# PCB_Draft_3.net
KiCad netlist of a schematic drawn in EAGLE
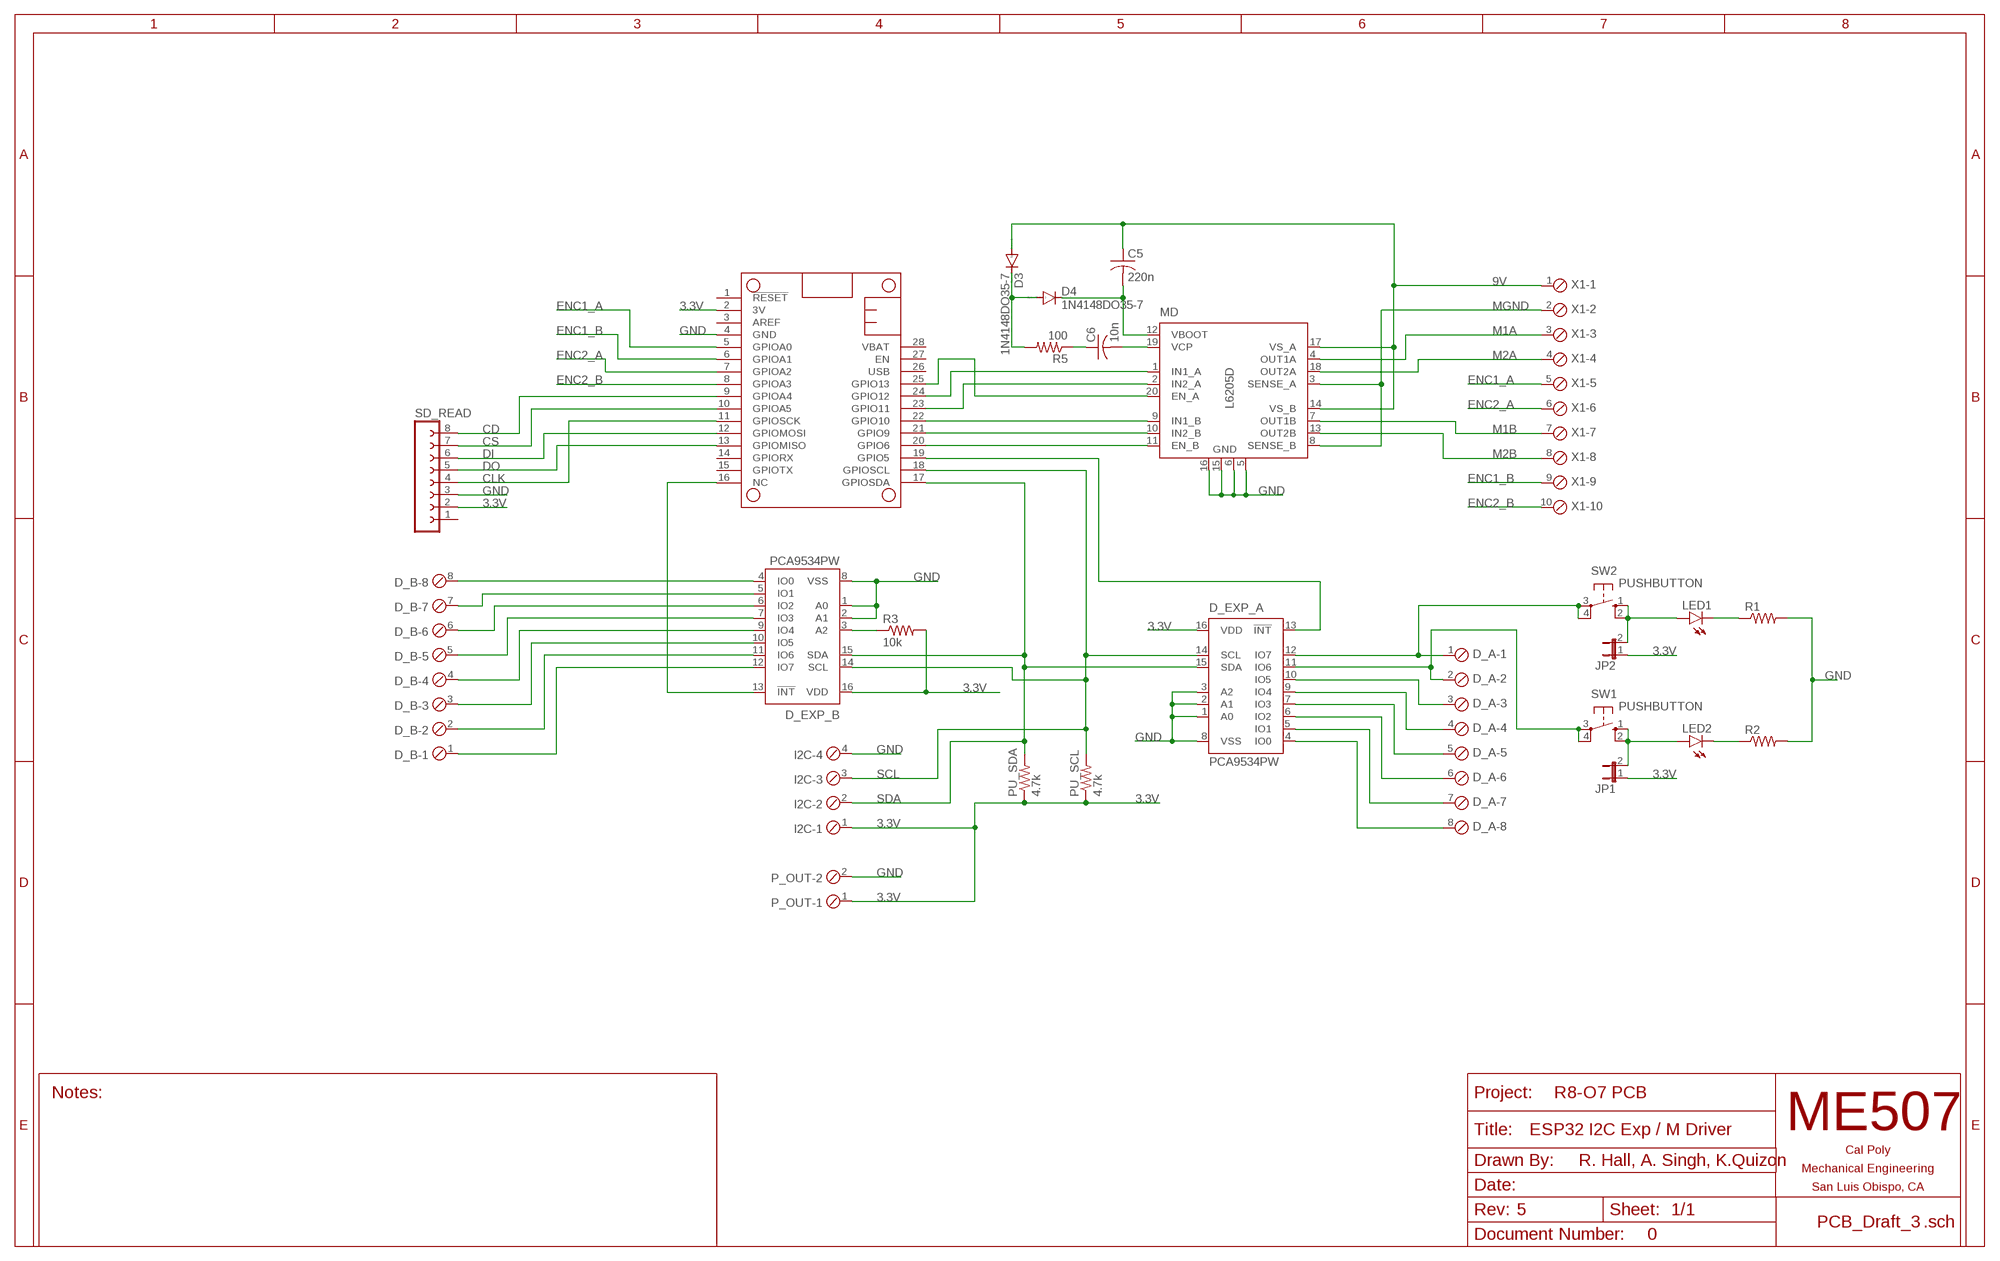
[diagram p0: schematic, sheet 1]

(export (version "E")
  (design (tool "Eeschema 10.0.6"))
  (components
    (comp (ref "C5")
      (value "220n")
      (footprint "eagle-import:C0805")
      (libsource (lib "eagle-import") (part "C-USC0805"))
    )
    (comp (ref "C6")
      (value "10n")
      (footprint "eagle-import:C0805")
      (libsource (lib "eagle-import") (part "C-USC0805"))
    )
    (comp (ref "D3")
      (value "1N4148DO35-7")
      (footprint "eagle-import:DO35-7")
      (libsource (lib "eagle-import") (part "1N4148DO35-7"))
    )
    (comp (ref "D4")
      (value "1N4148DO35-7")
      (footprint "eagle-import:DO35-7")
      (libsource (lib "eagle-import") (part "1N4148DO35-7"))
    )
    (comp (ref "D_A")
      (value "SCREWTERM_8P_254")
      (footprint "eagle-import:8POL254")
      (libsource (lib "eagle-import") (part "SCREWTERM_8P_254"))
    )
    (comp (ref "D_B")
      (value "SCREWTERM_8P_254")
      (footprint "eagle-import:8POL254")
      (libsource (lib "eagle-import") (part "SCREWTERM_8P_254"))
    )
    (comp (ref "D_EXP_A")
      (value "PCA9534PW")
      (footprint "eagle-import:TSSOP16")
      (libsource (lib "eagle-import") (part "PCA9534PW"))
    )
    (comp (ref "D_EXP_B")
      (value "PCA9534PW")
      (footprint "eagle-import:TSSOP16")
      (libsource (lib "eagle-import") (part "PCA9534PW"))
    )
    (comp (ref "FTHRWNG")
      (value "FEATHERWINGEXTENDED_BOTH_ENDS")
      (footprint "eagle-import:FEATHERWING")
      (libsource (lib "eagle-import") (part "FEATHERWINGEXTENDED_BOTH_ENDS"))
    )
    (comp (ref "I2C")
      (value "SCREWTERM_4P_254")
      (footprint "eagle-import:4POL254")
      (libsource (lib "eagle-import") (part "SCREWTERM_4P_254"))
    )
    (comp (ref "JP1")
      (value "JP1E")
      (footprint "eagle-import:JP1")
      (libsource (lib "eagle-import") (part "JP1E"))
    )
    (comp (ref "JP2")
      (value "JP1E")
      (footprint "eagle-import:JP1")
      (libsource (lib "eagle-import") (part "JP1E"))
    )
    (comp (ref "LED1")
      (value "LEDCHIPLED_0805")
      (footprint "eagle-import:CHIPLED_0805")
      (libsource (lib "eagle-import") (part "LEDCHIPLED_0805"))
    )
    (comp (ref "LED2")
      (value "LEDCHIPLED_0805")
      (footprint "eagle-import:CHIPLED_0805")
      (libsource (lib "eagle-import") (part "LEDCHIPLED_0805"))
    )
    (comp (ref "MD")
      (value "L6205D")
      (footprint "eagle-import:SO20")
      (libsource (lib "eagle-import") (part "L6205D"))
    )
    (comp (ref "PU_SCL")
      (value "4.7k")
      (footprint "eagle-import:M0805")
      (libsource (lib "eagle-import") (part "R-US_M0805"))
    )
    (comp (ref "PU_SDA")
      (value "4.7k")
      (footprint "eagle-import:M0805")
      (libsource (lib "eagle-import") (part "R-US_M0805"))
    )
    (comp (ref "P_OUT")
      (value "SCREWTERM_2P_254")
      (footprint "eagle-import:2POL254")
      (libsource (lib "eagle-import") (part "SCREWTERM_2P_254"))
    )
    (comp (ref "R1")
      (value "R-US_M0805")
      (footprint "eagle-import:M0805")
      (libsource (lib "eagle-import") (part "R-US_M0805"))
    )
    (comp (ref "R2")
      (value "R-US_M0805")
      (footprint "eagle-import:M0805")
      (libsource (lib "eagle-import") (part "R-US_M0805"))
    )
    (comp (ref "R3")
      (value "10k")
      (footprint "eagle-import:M0805")
      (libsource (lib "eagle-import") (part "R-US_M0805"))
    )
    (comp (ref "R5")
      (value "100")
      (footprint "eagle-import:M0805")
      (libsource (lib "eagle-import") (part "R-US_M0805"))
    )
    (comp (ref "SD_READ")
      (value "FE08-1")
      (footprint "eagle-import:FE08")
      (libsource (lib "eagle-import") (part "FE08-1"))
    )
    (comp (ref "SW1")
      (value "PUSHBUTTON")
      (footprint "eagle-import:B3F-10XX")
      (fields (field (name "MPN") "B3F-1000"))
      (libsource (lib "eagle-import") (part "PUSHBUTTON"))
    )
    (comp (ref "SW2")
      (value "PUSHBUTTON")
      (footprint "eagle-import:B3F-10XX")
      (fields (field (name "MPN") "B3F-1000"))
      (libsource (lib "eagle-import") (part "PUSHBUTTON"))
    )
    (comp (ref "X1")
      (value "SCREWTERM_10P_254")
      (footprint "eagle-import:10POL254")
      (libsource (lib "eagle-import") (part "SCREWTERM_10P_254"))
    )
  )
  (nets
    (net (code "1") (name "/3.3V") (class "Default")
      (node (ref "D_EXP_A") (pin "16") (pinfunction "VDD_16") (pintype "power_in"))
      (node (ref "D_EXP_B") (pin "16") (pinfunction "VDD_16") (pintype "power_in"))
      (node (ref "FTHRWNG") (pin "2") (pinfunction "3V_2") (pintype "power_in"))
      (node (ref "I2C") (pin "1") (pinfunction "1_1") (pintype "passive"))
      (node (ref "JP1") (pin "1") (pinfunction "1_1") (pintype "passive"))
      (node (ref "JP2") (pin "1") (pinfunction "1_1") (pintype "passive"))
      (node (ref "PU_SCL") (pin "1") (pinfunction "1_1") (pintype "passive"))
      (node (ref "PU_SDA") (pin "1") (pinfunction "1_1") (pintype "passive"))
      (node (ref "P_OUT") (pin "1") (pinfunction "1_1") (pintype "passive"))
      (node (ref "R3") (pin "2") (pinfunction "2_2") (pintype "passive"))
      (node (ref "SD_READ") (pin "2") (pinfunction "2_2") (pintype "passive"))
    )
    (net (code "2") (name "/9V") (class "Default")
      (node (ref "C5") (pin "1") (pinfunction "1_1") (pintype "passive"))
      (node (ref "D3") (pin "A") (pinfunction "A_A") (pintype "passive"))
      (node (ref "MD") (pin "14") (pinfunction "VS_B_14") (pintype "power_in"))
      (node (ref "MD") (pin "17") (pinfunction "VS_A_17") (pintype "power_in"))
      (node (ref "X1") (pin "1") (pinfunction "1_1") (pintype "passive"))
    )
    (net (code "3") (name "/CD") (class "Default")
      (node (ref "FTHRWNG") (pin "9") (pinfunction "GPIOA4_9") (pintype "bidirectional"))
      (node (ref "SD_READ") (pin "8") (pinfunction "8_8") (pintype "passive"))
    )
    (net (code "4") (name "/CLK") (class "Default")
      (node (ref "FTHRWNG") (pin "11") (pinfunction "GPIOSCK_11") (pintype "bidirectional"))
      (node (ref "SD_READ") (pin "4") (pinfunction "4_4") (pintype "passive"))
    )
    (net (code "5") (name "/CS") (class "Default")
      (node (ref "FTHRWNG") (pin "10") (pinfunction "GPIOA5_10") (pintype "bidirectional"))
      (node (ref "SD_READ") (pin "7") (pinfunction "7_7") (pintype "passive"))
    )
    (net (code "6") (name "/DI") (class "Default")
      (node (ref "FTHRWNG") (pin "12") (pinfunction "GPIOMOSI_12") (pintype "bidirectional"))
      (node (ref "SD_READ") (pin "6") (pinfunction "6_6") (pintype "passive"))
    )
    (net (code "7") (name "/DO") (class "Default")
      (node (ref "FTHRWNG") (pin "13") (pinfunction "GPIOMISO_13") (pintype "bidirectional"))
      (node (ref "SD_READ") (pin "5") (pinfunction "5_5") (pintype "passive"))
    )
    (net (code "8") (name "/ENC1_A") (class "Default")
      (node (ref "FTHRWNG") (pin "5") (pinfunction "GPIOA0_5") (pintype "bidirectional"))
      (node (ref "X1") (pin "5") (pinfunction "1_5") (pintype "passive"))
    )
    (net (code "9") (name "/ENC1_B") (class "Default")
      (node (ref "FTHRWNG") (pin "6") (pinfunction "GPIOA1_6") (pintype "bidirectional"))
      (node (ref "X1") (pin "9") (pinfunction "1_9") (pintype "passive"))
    )
    (net (code "10") (name "/ENC2_A") (class "Default")
      (node (ref "FTHRWNG") (pin "7") (pinfunction "GPIOA2_7") (pintype "bidirectional"))
      (node (ref "X1") (pin "6") (pinfunction "1_6") (pintype "passive"))
    )
    (net (code "11") (name "/ENC2_B") (class "Default")
      (node (ref "FTHRWNG") (pin "8") (pinfunction "GPIOA3_8") (pintype "bidirectional"))
      (node (ref "X1") (pin "10") (pinfunction "1_10") (pintype "passive"))
    )
    (net (code "12") (name "/GND") (class "Default")
      (node (ref "D_EXP_A") (pin "1") (pinfunction "A0_1") (pintype "input"))
      (node (ref "D_EXP_A") (pin "2") (pinfunction "A1_2") (pintype "input"))
      (node (ref "D_EXP_A") (pin "3") (pinfunction "A2_3") (pintype "input"))
      (node (ref "D_EXP_A") (pin "8") (pinfunction "VSS_8") (pintype "power_in"))
      (node (ref "D_EXP_B") (pin "1") (pinfunction "A0_1") (pintype "input"))
      (node (ref "D_EXP_B") (pin "2") (pinfunction "A1_2") (pintype "input"))
      (node (ref "D_EXP_B") (pin "8") (pinfunction "VSS_8") (pintype "power_in"))
      (node (ref "FTHRWNG") (pin "4") (pinfunction "GND_4") (pintype "power_in"))
      (node (ref "I2C") (pin "4") (pinfunction "1_4") (pintype "passive"))
      (node (ref "MD") (pin "15") (pinfunction "GND_15") (pintype "power_in"))
      (node (ref "MD") (pin "16") (pinfunction "GND_16") (pintype "power_in"))
      (node (ref "MD") (pin "5") (pinfunction "GND_5") (pintype "power_in"))
      (node (ref "MD") (pin "6") (pinfunction "GND_6") (pintype "power_in"))
      (node (ref "P_OUT") (pin "2") (pinfunction "1_2") (pintype "passive"))
      (node (ref "R1") (pin "2") (pinfunction "2_2") (pintype "passive"))
      (node (ref "R2") (pin "2") (pinfunction "2_2") (pintype "passive"))
      (node (ref "SD_READ") (pin "3") (pinfunction "3_3") (pintype "passive"))
    )
    (net (code "13") (name "/M1A") (class "Default")
      (node (ref "MD") (pin "4") (pinfunction "OUT1A_4") (pintype "output"))
      (node (ref "X1") (pin "3") (pinfunction "1_3") (pintype "passive"))
    )
    (net (code "14") (name "/M1B") (class "Default")
      (node (ref "MD") (pin "7") (pinfunction "OUT1B_7") (pintype "output"))
      (node (ref "X1") (pin "7") (pinfunction "1_7") (pintype "passive"))
    )
    (net (code "15") (name "/M2A") (class "Default")
      (node (ref "MD") (pin "18") (pinfunction "OUT2A_18") (pintype "output"))
      (node (ref "X1") (pin "4") (pinfunction "1_4") (pintype "passive"))
    )
    (net (code "16") (name "/M2B") (class "Default")
      (node (ref "MD") (pin "13") (pinfunction "OUT2B_13") (pintype "output"))
      (node (ref "X1") (pin "8") (pinfunction "1_8") (pintype "passive"))
    )
    (net (code "17") (name "/MGND") (class "Default")
      (node (ref "MD") (pin "3") (pinfunction "SENSE_A_3") (pintype "input"))
      (node (ref "MD") (pin "8") (pinfunction "SENSE_B_8") (pintype "input"))
      (node (ref "X1") (pin "2") (pinfunction "1_2") (pintype "passive"))
    )
    (net (code "18") (name "/SCL") (class "Default")
      (node (ref "D_EXP_A") (pin "14") (pinfunction "SCL_14") (pintype "input"))
      (node (ref "D_EXP_B") (pin "14") (pinfunction "SCL_14") (pintype "input"))
      (node (ref "FTHRWNG") (pin "18") (pinfunction "GPIOSCL_18") (pintype "bidirectional"))
      (node (ref "I2C") (pin "3") (pinfunction "1_3") (pintype "passive"))
      (node (ref "PU_SCL") (pin "2") (pinfunction "2_2") (pintype "passive"))
    )
    (net (code "19") (name "/SDA") (class "Default")
      (node (ref "D_EXP_A") (pin "15") (pinfunction "SDA_15") (pintype "bidirectional"))
      (node (ref "D_EXP_B") (pin "15") (pinfunction "SDA_15") (pintype "bidirectional"))
      (node (ref "FTHRWNG") (pin "17") (pinfunction "GPIOSDA_17") (pintype "bidirectional"))
      (node (ref "I2C") (pin "2") (pinfunction "1_2") (pintype "passive"))
      (node (ref "PU_SDA") (pin "2") (pinfunction "2_2") (pintype "passive"))
    )
    (net (code "20") (name "/USB") (class "Default")
      (node (ref "FTHRWNG") (pin "26") (pinfunction "USB_26") (pintype "power_in"))
    )
    (net (code "21") (name "/VBAT") (class "Default")
      (node (ref "FTHRWNG") (pin "28") (pinfunction "VBAT_28") (pintype "power_in"))
    )
    (net (code "22") (name "Net-(C6-Pad1)") (class "Default")
      (node (ref "C6") (pin "1") (pinfunction "1_1") (pintype "passive"))
      (node (ref "R5") (pin "1") (pinfunction "1_1") (pintype "passive"))
    )
    (net (code "23") (name "Net-(D3-PadC)") (class "Default")
      (node (ref "D3") (pin "C") (pinfunction "C_C") (pintype "passive"))
      (node (ref "D4") (pin "A") (pinfunction "A_A") (pintype "passive"))
      (node (ref "R5") (pin "2") (pinfunction "2_2") (pintype "passive"))
    )
    (net (code "24") (name "Net-(D_AB-1)") (class "Default")
      (node (ref "D_A") (pin "2") (pinfunction "1_2") (pintype "passive"))
      (node (ref "D_EXP_A") (pin "11") (pinfunction "IO6_11") (pintype "bidirectional"))
      (node (ref "SW1") (pin "3") (pinfunction "P_3") (pintype "passive"))
      (node (ref "SW1") (pin "4") (pinfunction "P1_4") (pintype "passive"))
    )
    (net (code "25") (name "Net-(D_AC-1)") (class "Default")
      (node (ref "D_A") (pin "3") (pinfunction "1_3") (pintype "passive"))
      (node (ref "D_EXP_A") (pin "10") (pinfunction "IO5_10") (pintype "bidirectional"))
    )
    (net (code "26") (name "Net-(D_AD-1)") (class "Default")
      (node (ref "D_A") (pin "4") (pinfunction "1_4") (pintype "passive"))
      (node (ref "D_EXP_A") (pin "9") (pinfunction "IO4_9") (pintype "bidirectional"))
    )
    (net (code "27") (name "Net-(D_AE-1)") (class "Default")
      (node (ref "D_A") (pin "5") (pinfunction "1_5") (pintype "passive"))
      (node (ref "D_EXP_A") (pin "7") (pinfunction "IO3_7") (pintype "bidirectional"))
    )
    (net (code "28") (name "Net-(D_AF-1)") (class "Default")
      (node (ref "D_A") (pin "6") (pinfunction "1_6") (pintype "passive"))
      (node (ref "D_EXP_A") (pin "6") (pinfunction "IO2_6") (pintype "bidirectional"))
    )
    (net (code "29") (name "Net-(D_AG-1)") (class "Default")
      (node (ref "D_A") (pin "7") (pinfunction "1_7") (pintype "passive"))
      (node (ref "D_EXP_A") (pin "5") (pinfunction "IO1_5") (pintype "bidirectional"))
    )
    (net (code "30") (name "Net-(D_AH-1)") (class "Default")
      (node (ref "D_A") (pin "8") (pinfunction "1_8") (pintype "passive"))
      (node (ref "D_EXP_A") (pin "4") (pinfunction "IO0_4") (pintype "bidirectional"))
    )
    (net (code "31") (name "Net-(D_BB-1)") (class "Default")
      (node (ref "D_B") (pin "2") (pinfunction "1_2") (pintype "passive"))
      (node (ref "D_EXP_B") (pin "11") (pinfunction "IO6_11") (pintype "bidirectional"))
    )
    (net (code "32") (name "Net-(D_BC-1)") (class "Default")
      (node (ref "D_B") (pin "3") (pinfunction "1_3") (pintype "passive"))
      (node (ref "D_EXP_B") (pin "10") (pinfunction "IO5_10") (pintype "bidirectional"))
    )
    (net (code "33") (name "Net-(D_BD-1)") (class "Default")
      (node (ref "D_B") (pin "4") (pinfunction "1_4") (pintype "passive"))
      (node (ref "D_EXP_B") (pin "9") (pinfunction "IO4_9") (pintype "bidirectional"))
    )
    (net (code "34") (name "Net-(D_BE-1)") (class "Default")
      (node (ref "D_B") (pin "5") (pinfunction "1_5") (pintype "passive"))
      (node (ref "D_EXP_B") (pin "7") (pinfunction "IO3_7") (pintype "bidirectional"))
    )
    (net (code "35") (name "Net-(D_BF-1)") (class "Default")
      (node (ref "D_B") (pin "6") (pinfunction "1_6") (pintype "passive"))
      (node (ref "D_EXP_B") (pin "6") (pinfunction "IO2_6") (pintype "bidirectional"))
    )
    (net (code "36") (name "Net-(D_BG-1)") (class "Default")
      (node (ref "D_B") (pin "7") (pinfunction "1_7") (pintype "passive"))
      (node (ref "D_EXP_B") (pin "5") (pinfunction "IO1_5") (pintype "bidirectional"))
    )
    (net (code "37") (name "Net-(D_BH-1)") (class "Default")
      (node (ref "D_B") (pin "8") (pinfunction "1_8") (pintype "passive"))
      (node (ref "D_EXP_B") (pin "4") (pinfunction "IO0_4") (pintype "bidirectional"))
    )
    (net (code "38") (name "Net-(D_EXP_A-IO7)") (class "Default")
      (node (ref "D_A") (pin "1") (pinfunction "1_1") (pintype "passive"))
      (node (ref "D_EXP_A") (pin "12") (pinfunction "IO7_12") (pintype "bidirectional"))
      (node (ref "SW2") (pin "3") (pinfunction "P_3") (pintype "passive"))
      (node (ref "SW2") (pin "4") (pinfunction "P1_4") (pintype "passive"))
    )
    (net (code "39") (name "Net-(D_EXP_A-~{INT})") (class "Default")
      (node (ref "D_EXP_A") (pin "13") (pinfunction "~{INT}_13") (pintype "open_collector"))
      (node (ref "FTHRWNG") (pin "19") (pinfunction "GPIO5_19") (pintype "bidirectional"))
    )
    (net (code "40") (name "Net-(D_EXP_B-A2)") (class "Default")
      (node (ref "D_EXP_B") (pin "3") (pinfunction "A2_3") (pintype "input"))
      (node (ref "R3") (pin "1") (pinfunction "1_1") (pintype "passive"))
    )
    (net (code "41") (name "Net-(D_EXP_B-IO7)") (class "Default")
      (node (ref "D_B") (pin "1") (pinfunction "1_1") (pintype "passive"))
      (node (ref "D_EXP_B") (pin "12") (pinfunction "IO7_12") (pintype "bidirectional"))
    )
    (net (code "42") (name "Net-(D_EXP_B-~{INT})") (class "Default")
      (node (ref "D_EXP_B") (pin "13") (pinfunction "~{INT}_13") (pintype "open_collector"))
      (node (ref "FTHRWNG") (pin "16") (pinfunction "NC_16") (pintype "passive"))
    )
    (net (code "43") (name "Net-(FTHRWNG-GPIO6)") (class "Default")
      (node (ref "FTHRWNG") (pin "20") (pinfunction "GPIO6_20") (pintype "bidirectional"))
      (node (ref "MD") (pin "11") (pinfunction "EN_B_11") (pintype "input"))
    )
    (net (code "44") (name "Net-(FTHRWNG-GPIO9)") (class "Default")
      (node (ref "FTHRWNG") (pin "21") (pinfunction "GPIO9_21") (pintype "bidirectional"))
      (node (ref "MD") (pin "10") (pinfunction "IN2_B_10") (pintype "input"))
    )
    (net (code "45") (name "Net-(FTHRWNG-GPIO10)") (class "Default")
      (node (ref "FTHRWNG") (pin "22") (pinfunction "GPIO10_22") (pintype "bidirectional"))
      (node (ref "MD") (pin "9") (pinfunction "IN1_B_9") (pintype "input"))
    )
    (net (code "46") (name "Net-(FTHRWNG-GPIO11)") (class "Default")
      (node (ref "FTHRWNG") (pin "23") (pinfunction "GPIO11_23") (pintype "bidirectional"))
      (node (ref "MD") (pin "2") (pinfunction "IN2_A_2") (pintype "input"))
    )
    (net (code "47") (name "Net-(FTHRWNG-GPIO12)") (class "Default")
      (node (ref "FTHRWNG") (pin "24") (pinfunction "GPIO12_24") (pintype "bidirectional"))
      (node (ref "MD") (pin "1") (pinfunction "IN1_A_1") (pintype "input"))
    )
    (net (code "48") (name "Net-(FTHRWNG-GPIO13)") (class "Default")
      (node (ref "FTHRWNG") (pin "25") (pinfunction "GPIO13_25") (pintype "bidirectional"))
      (node (ref "MD") (pin "20") (pinfunction "EN_A_20") (pintype "input"))
    )
    (net (code "49") (name "Net-(LED1-PadC)") (class "Default")
      (node (ref "LED1") (pin "C") (pinfunction "C_C") (pintype "passive"))
      (node (ref "R1") (pin "1") (pinfunction "1_1") (pintype "passive"))
    )
    (net (code "50") (name "Net-(LED2-PadC)") (class "Default")
      (node (ref "LED2") (pin "C") (pinfunction "C_C") (pintype "passive"))
      (node (ref "R2") (pin "1") (pinfunction "1_1") (pintype "passive"))
    )
    (net (code "51") (name "Net-(MD-VBOOT)") (class "Default")
      (node (ref "C5") (pin "2") (pinfunction "2_2") (pintype "passive"))
      (node (ref "D4") (pin "C") (pinfunction "C_C") (pintype "passive"))
      (node (ref "MD") (pin "12") (pinfunction "VBOOT_12") (pintype "power_in"))
    )
    (net (code "52") (name "Net-(MD-VCP)") (class "Default")
      (node (ref "C6") (pin "2") (pinfunction "2_2") (pintype "passive"))
      (node (ref "MD") (pin "19") (pinfunction "VCP_19") (pintype "power_in"))
    )
    (net (code "53") (name "Net-(SW1-S)") (class "Default")
      (node (ref "JP1") (pin "2") (pinfunction "2_2") (pintype "passive"))
      (node (ref "LED2") (pin "A") (pinfunction "A_A") (pintype "passive"))
      (node (ref "SW1") (pin "1") (pinfunction "S_1") (pintype "passive"))
      (node (ref "SW1") (pin "2") (pinfunction "S1_2") (pintype "passive"))
    )
    (net (code "54") (name "Net-(SW2-S)") (class "Default")
      (node (ref "JP2") (pin "2") (pinfunction "2_2") (pintype "passive"))
      (node (ref "LED1") (pin "A") (pinfunction "A_A") (pintype "passive"))
      (node (ref "SW2") (pin "1") (pinfunction "S_1") (pintype "passive"))
      (node (ref "SW2") (pin "2") (pinfunction "S1_2") (pintype "passive"))
    )
    (net (code "55") (name "unconnected-(FTHRWNG-AREF-Pad3)") (class "Default")
      (node (ref "FTHRWNG") (pin "3") (pinfunction "AREF_3") (pintype "passive"))
    )
    (net (code "56") (name "unconnected-(FTHRWNG-EN-Pad27)") (class "Default")
      (node (ref "FTHRWNG") (pin "27") (pinfunction "EN_27") (pintype "passive"))
    )
    (net (code "57") (name "unconnected-(FTHRWNG-GPIORX-Pad14)") (class "Default")
      (node (ref "FTHRWNG") (pin "14") (pinfunction "GPIORX_14") (pintype "bidirectional"))
    )
    (net (code "58") (name "unconnected-(FTHRWNG-GPIOTX-Pad15)") (class "Default")
      (node (ref "FTHRWNG") (pin "15") (pinfunction "GPIOTX_15") (pintype "bidirectional"))
    )
    (net (code "59") (name "unconnected-(FTHRWNG-~{RESET}-Pad1)") (class "Default")
      (node (ref "FTHRWNG") (pin "1") (pinfunction "~{RESET}_1") (pintype "input"))
    )
    (net (code "60") (name "unconnected-(SD_READ-Pad1)") (class "Default")
      (node (ref "SD_READ") (pin "1") (pinfunction "1_1") (pintype "passive"))
    )
  )
)
